# HDMI.net
KiCad netlist of a schematic drawn in Altium Designer
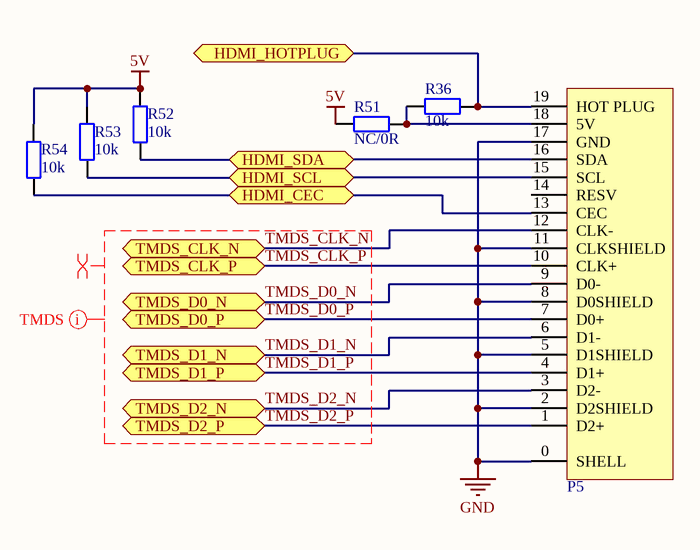
[diagram p0: HDMI.SchDoc]

(export (version "E")
  (design (tool "Eeschema 10.0.6"))
  (components
    (comp (ref "P5") (value "HDMI") (footprint "HDMI") (libsource (lib "sch") (part "HDMI")))
    (comp (ref "R36")
      (value "10k")
      (footprint "0402")
      (description "Resistor")
      (fields (field (name "PUBLISHER") "Altium Limited"))
      (libsource (lib "") (part "Res2_2"))
    )
    (comp (ref "R51")
      (value "NC/0R")
      (footprint "0402")
      (description "Resistor")
      (fields (field (name "PUBLISHER") "Altium Limited"))
      (libsource (lib "") (part "Res2_1"))
    )
    (comp (ref "R52")
      (value "10k")
      (footprint "0402")
      (description "Resistor")
      (fields (field (name "PUBLISHER") "Altium Limited"))
      (libsource (lib "Miscellaneous Devices") (part "Res2"))
    )
    (comp (ref "R53")
      (value "10k")
      (footprint "0402")
      (description "Resistor")
      (fields (field (name "PUBLISHER") "Altium Limited"))
      (libsource (lib "Miscellaneous Devices") (part "Res2"))
    )
    (comp (ref "R54")
      (value "10k")
      (footprint "0402")
      (description "Resistor")
      (fields (field (name "PUBLISHER") "Altium Limited"))
      (libsource (lib "Miscellaneous Devices") (part "Res2"))
    )
  )
  (nets
    (net (code "1") (name "/HDMI_CEC") (class "Default")
      (node (ref "P5") (pin "13") (pinfunction "CEC_13") (pintype "passive"))
      (node (ref "R54") (pin "2") (pinfunction "2_2") (pintype "passive"))
    )
    (net (code "2") (name "/HDMI_HOTPLUG") (class "Default")
      (node (ref "P5") (pin "19") (pinfunction "HOT_PLUG_19") (pintype "passive"))
      (node (ref "R36") (pin "1") (pinfunction "1_1") (pintype "passive"))
    )
    (net (code "3") (name "/HDMI_SCL") (class "Default")
      (node (ref "P5") (pin "15") (pinfunction "SCL_15") (pintype "passive"))
      (node (ref "R53") (pin "2") (pinfunction "2_2") (pintype "passive"))
    )
    (net (code "4") (name "/HDMI_SDA") (class "Default")
      (node (ref "P5") (pin "16") (pinfunction "SDA_16") (pintype "passive"))
      (node (ref "R52") (pin "2") (pinfunction "2_2") (pintype "passive"))
    )
    (net (code "5") (name "/TMDS_CLK_N") (class "Default")
      (node (ref "P5") (pin "12") (pinfunction "CLK-_12") (pintype "passive"))
    )
    (net (code "6") (name "/TMDS_CLK_P") (class "Default")
      (node (ref "P5") (pin "10") (pinfunction "CLK+_10") (pintype "passive"))
    )
    (net (code "7") (name "/TMDS_D0_N") (class "Default")
      (node (ref "P5") (pin "9") (pinfunction "D0-_9") (pintype "passive"))
    )
    (net (code "8") (name "/TMDS_D0_P") (class "Default")
      (node (ref "P5") (pin "7") (pinfunction "D0+_7") (pintype "passive"))
    )
    (net (code "9") (name "/TMDS_D1_N") (class "Default")
      (node (ref "P5") (pin "6") (pinfunction "D1-_6") (pintype "passive"))
    )
    (net (code "10") (name "/TMDS_D1_P") (class "Default")
      (node (ref "P5") (pin "4") (pinfunction "D1+_4") (pintype "passive"))
    )
    (net (code "11") (name "/TMDS_D2_N") (class "Default")
      (node (ref "P5") (pin "3") (pinfunction "D2-_3") (pintype "passive"))
    )
    (net (code "12") (name "/TMDS_D2_P") (class "Default")
      (node (ref "P5") (pin "1") (pinfunction "D2+_1") (pintype "passive"))
    )
    (net (code "13") (name "5V") (class "Default")
      (node (ref "R51") (pin "1") (pinfunction "1_1") (pintype "passive"))
      (node (ref "R52") (pin "1") (pinfunction "1_1") (pintype "passive"))
      (node (ref "R53") (pin "1") (pinfunction "1_1") (pintype "passive"))
      (node (ref "R54") (pin "1") (pinfunction "1_1") (pintype "passive"))
    )
    (net (code "14") (name "GND") (class "Default")
      (node (ref "P5") (pin "0") (pinfunction "SHELL_0") (pintype "passive"))
      (node (ref "P5") (pin "11") (pinfunction "CLKSHIELD_11") (pintype "passive"))
      (node (ref "P5") (pin "17") (pinfunction "GND_17") (pintype "passive"))
      (node (ref "P5") (pin "2") (pinfunction "D2SHIELD_2") (pintype "passive"))
      (node (ref "P5") (pin "5") (pinfunction "D1SHIELD_5") (pintype "passive"))
      (node (ref "P5") (pin "8") (pinfunction "D0SHIELD_8") (pintype "passive"))
    )
    (net (code "15") (name "Net-(P5-5V)") (class "Default")
      (node (ref "P5") (pin "18") (pinfunction "5V_18") (pintype "passive"))
      (node (ref "R36") (pin "2") (pinfunction "2_2") (pintype "passive"))
      (node (ref "R51") (pin "2") (pinfunction "2_2") (pintype "passive"))
    )
    (net (code "16") (name "unconnected-(P5-RESV-Pad14)") (class "Default")
      (node (ref "P5") (pin "14") (pinfunction "RESV_14") (pintype "passive"))
    )
  )
)
